# vme_sys_buff.net
KiCad netlist of a schematic drawn in Altium Designer
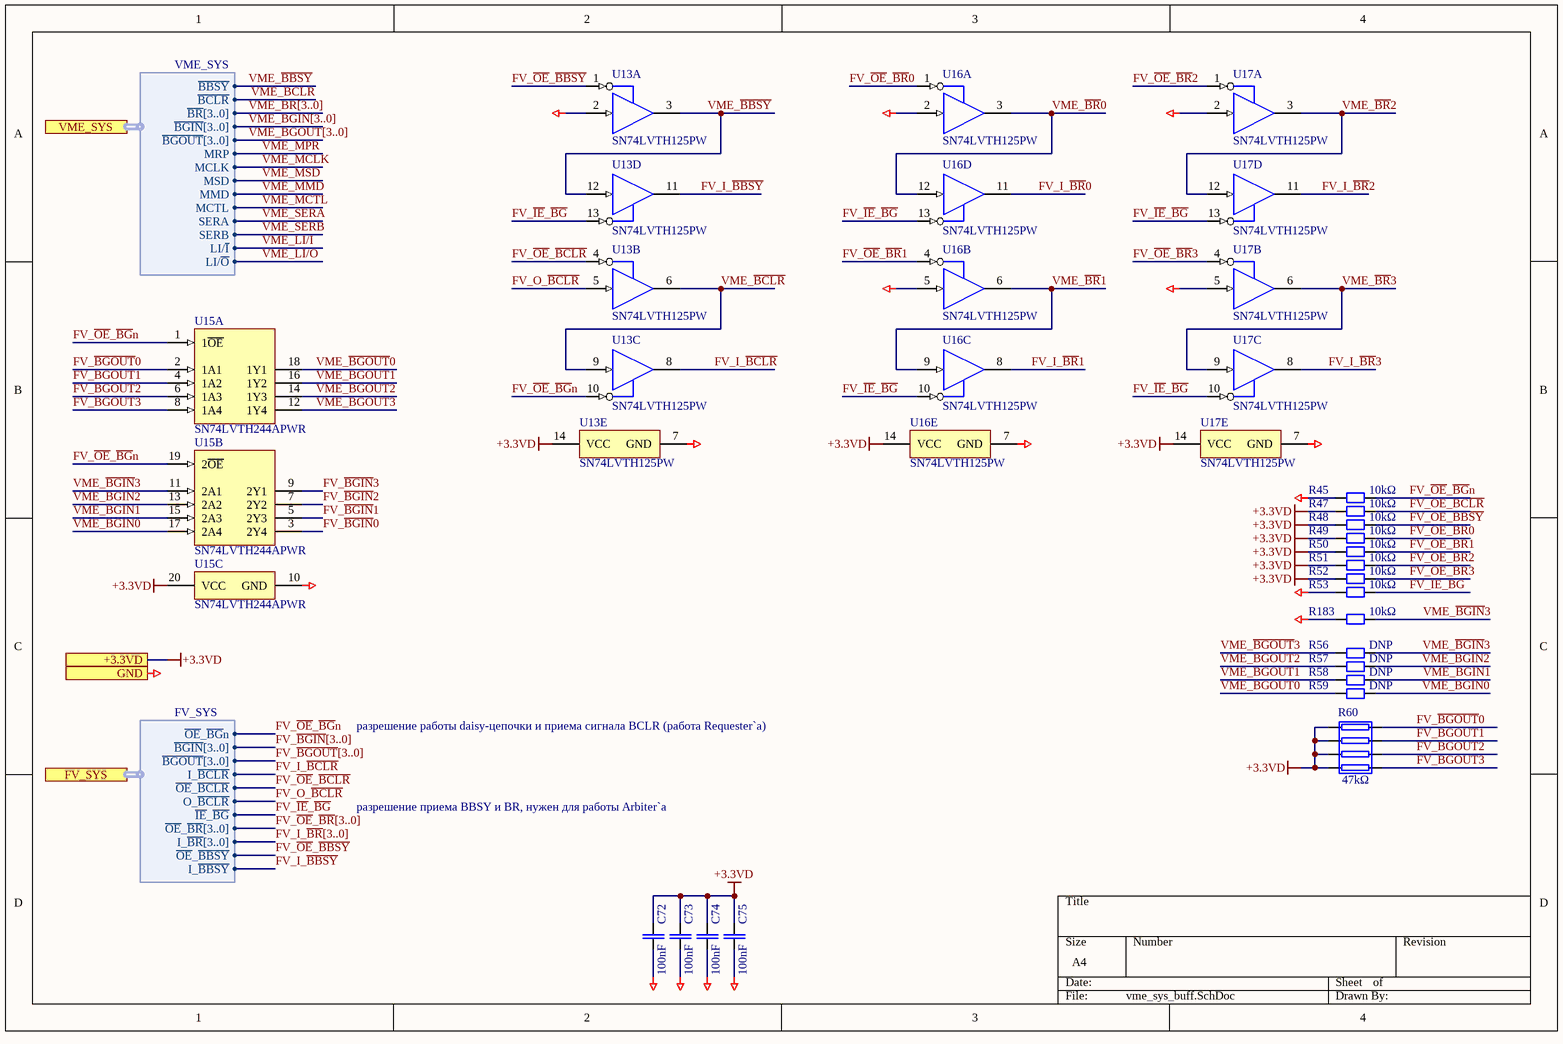
[diagram p0: vme_sys_buff.SchDoc]

(export (version "E")
  (design (tool "Eeschema 10.0.6"))
  (components
    (comp (ref "C72")
      (value "100nF")
      (footprint "CAPC1608N")
      (description "Generic ceramic SMD capacitor")
      (fields (field (name "MAINTAINER") "Evgeniy Kotov"))
      (libsource (lib "[Capacitors] Capacitors SMD") (part "CAPC"))
    )
    (comp (ref "C73")
      (value "100nF")
      (footprint "CAPC1608N")
      (description "Generic ceramic SMD capacitor")
      (fields (field (name "MAINTAINER") "Evgeniy Kotov"))
      (libsource (lib "[Capacitors] Capacitors SMD") (part "CAPC"))
    )
    (comp (ref "C74")
      (value "100nF")
      (footprint "CAPC1608N")
      (description "Generic ceramic SMD capacitor")
      (fields (field (name "MAINTAINER") "Evgeniy Kotov"))
      (libsource (lib "[Capacitors] Capacitors SMD") (part "CAPC"))
    )
    (comp (ref "C75")
      (value "100nF")
      (footprint "CAPC1608N")
      (description "Generic ceramic SMD capacitor")
      (fields (field (name "MAINTAINER") "Evgeniy Kotov"))
      (libsource (lib "[Capacitors] Capacitors SMD") (part "CAPC"))
    )
    (comp (ref "R45")
      (value "10kΩ")
      (footprint "RESC2012N")
      (description "Resistor, Generic, SMD")
      (fields (field (name "MAINTAINER") "Evgeniy Kotov"))
      (libsource (lib "[Resistors] Resistors SMD") (part "RESC"))
    )
    (comp (ref "R47")
      (value "10kΩ")
      (footprint "RESC2012N")
      (description "Resistor, Generic, SMD")
      (fields (field (name "MAINTAINER") "Evgeniy Kotov"))
      (libsource (lib "[Resistors] Resistors SMD") (part "RESC"))
    )
    (comp (ref "R48")
      (value "10kΩ")
      (footprint "RESC2012N")
      (description "Resistor, Generic, SMD")
      (fields (field (name "MAINTAINER") "Evgeniy Kotov"))
      (libsource (lib "[Resistors] Resistors SMD") (part "RESC"))
    )
    (comp (ref "R49")
      (value "10kΩ")
      (footprint "RESC2012N")
      (description "Resistor, Generic, SMD")
      (fields (field (name "MAINTAINER") "Evgeniy Kotov"))
      (libsource (lib "[Resistors] Resistors SMD") (part "RESC"))
    )
    (comp (ref "R50")
      (value "10kΩ")
      (footprint "RESC2012N")
      (description "Resistor, Generic, SMD")
      (fields (field (name "MAINTAINER") "Evgeniy Kotov"))
      (libsource (lib "[Resistors] Resistors SMD") (part "RESC"))
    )
    (comp (ref "R51")
      (value "10kΩ")
      (footprint "RESC2012N")
      (description "Resistor, Generic, SMD")
      (fields (field (name "MAINTAINER") "Evgeniy Kotov"))
      (libsource (lib "[Resistors] Resistors SMD") (part "RESC"))
    )
    (comp (ref "R52")
      (value "10kΩ")
      (footprint "RESC2012N")
      (description "Resistor, Generic, SMD")
      (fields (field (name "MAINTAINER") "Evgeniy Kotov"))
      (libsource (lib "[Resistors] Resistors SMD") (part "RESC"))
    )
    (comp (ref "R53")
      (value "10kΩ")
      (footprint "RESC2012N")
      (description "Resistor, Generic, SMD")
      (fields (field (name "MAINTAINER") "Evgeniy Kotov"))
      (libsource (lib "[Resistors] Resistors SMD") (part "RESC"))
    )
    (comp (ref "R56")
      (value "DNP")
      (footprint "RESC1608N")
      (description "Resistor, Generic, SMD")
      (fields (field (name "MAINTAINER") "Evgeniy Kotov"))
      (libsource (lib "[Resistors] Resistors SMD") (part "RESC"))
    )
    (comp (ref "R57")
      (value "DNP")
      (footprint "RESC1608N")
      (description "Resistor, Generic, SMD")
      (fields (field (name "MAINTAINER") "Evgeniy Kotov"))
      (libsource (lib "[Resistors] Resistors SMD") (part "RESC"))
    )
    (comp (ref "R58")
      (value "DNP")
      (footprint "RESC1608N")
      (description "Resistor, Generic, SMD")
      (fields (field (name "MAINTAINER") "Evgeniy Kotov"))
      (libsource (lib "[Resistors] Resistors SMD") (part "RESC"))
    )
    (comp (ref "R59")
      (value "DNP")
      (footprint "RESC1608N")
      (description "Resistor, Generic, SMD")
      (fields (field (name "MAINTAINER") "Evgeniy Kotov"))
      (libsource (lib "[Resistors] Resistors SMD") (part "RESC"))
    )
    (comp (ref "R60")
      (value "47kΩ")
      (footprint "CAY16-J4")
      (fields (field (name "Comment") "CAY16-4702F4LF") (field (name "MAINTAINER") "Anton Pavlenko"))
      (libsource (lib "[Resistors] Resistors SMD") (part "RESPACK4"))
    )
    (comp (ref "R183")
      (value "10kΩ")
      (footprint "RESC2012N")
      (description "Resistor, Generic, SMD")
      (fields (field (name "MAINTAINER") "Evgeniy Kotov"))
      (libsource (lib "[Resistors] Resistors SMD") (part "RESC"))
    )
    (comp (ref "U13")
      (value "SN74LVTH125PW")
      (footprint "PW0014A_N")
      (description "3.3-V ABT Quadruple Bus Buffers With 3-State Outputs, PW0014A, TUBE")
      (fields
        (field (name "MANUFACTURER") "Texas Instruments")
        (field (name "GENERIC PART NUMBER") "SN74LVTH125")
      )
      (libsource (lib "") (part "TI-SN74LVTH125-PW0014A-14_1"))
    )
    (comp (ref "U15")
      (value "SN74LVTH244APWR")
      (footprint "PW0020A_N")
      (description "3.3-V ABT Octal Buffers/Drivers With 3-State Outputs, PW0020A, LARGE T&R")
      (fields
        (field (name "GENERIC PART NUMBER") "SN74LVTH244A")
        (field (name "MANUFACTURER") "Texas Instruments")
      )
      (libsource (lib "Altium Content Vault") (part "TI-SN54_74-XX020A-20"))
    )
    (comp (ref "U16")
      (value "SN74LVTH125PW")
      (footprint "PW0014A_N")
      (description "3.3-V ABT Quadruple Bus Buffers With 3-State Outputs, PW0014A, TUBE")
      (fields
        (field (name "MANUFACTURER") "Texas Instruments")
        (field (name "GENERIC PART NUMBER") "SN74LVTH125")
      )
      (libsource (lib "Altium Content Vault") (part "TI-SN74LVTH125-PW0014A-14"))
    )
    (comp (ref "U17")
      (value "SN74LVTH125PW")
      (footprint "PW0014A_N")
      (description "3.3-V ABT Quadruple Bus Buffers With 3-State Outputs, PW0014A, TUBE")
      (fields
        (field (name "MANUFACTURER") "Texas Instruments")
        (field (name "GENERIC PART NUMBER") "SN74LVTH125")
      )
      (libsource (lib "") (part "TI-SN74LVTH125-PW0014A-14_1"))
    )
  )
  (nets
    (net (code "3") (name "+3.3VD") (class "Default")
      (node (ref "C72") (pin "2") (pintype "passive"))
      (node (ref "C73") (pin "2") (pintype "passive"))
      (node (ref "C74") (pin "2") (pintype "passive"))
      (node (ref "C75") (pin "2") (pintype "passive"))
      (node (ref "R47") (pin "1") (pintype "passive"))
      (node (ref "R48") (pin "1") (pintype "passive"))
      (node (ref "R49") (pin "1") (pintype "passive"))
      (node (ref "R50") (pin "1") (pintype "passive"))
      (node (ref "R51") (pin "1") (pintype "passive"))
      (node (ref "R52") (pin "1") (pintype "passive"))
      (node (ref "R60") (pin "1") (pinfunction "1_1") (pintype "passive"))
      (node (ref "R60") (pin "2") (pinfunction "2_2") (pintype "passive"))
      (node (ref "R60") (pin "3") (pinfunction "3_3") (pintype "passive"))
      (node (ref "R60") (pin "4") (pinfunction "4_4") (pintype "passive"))
      (node (ref "U13") (pin "14") (pinfunction "VCC_14") (pintype "power_in"))
      (node (ref "U15") (pin "20") (pinfunction "VCC_20") (pintype "power_in"))
      (node (ref "U16") (pin "14") (pinfunction "VCC_14") (pintype "power_in"))
      (node (ref "U17") (pin "14") (pinfunction "VCC_14") (pintype "power_in"))
    )
    (net (code "4") (name "/FV_I_~{BBSY}") (class "Default")
      (node (ref "U13") (pin "11") (pinfunction "4Y_11") (pintype "tri_state"))
    )
    (net (code "5") (name "/FV_I_~{BCLR}") (class "Default")
      (node (ref "U13") (pin "8") (pinfunction "3Y_8") (pintype "tri_state"))
    )
    (net (code "6") (name "/FV_I_~{BR}0") (class "Default")
      (node (ref "U16") (pin "11") (pinfunction "4Y_11") (pintype "tri_state"))
    )
    (net (code "7") (name "/FV_I_~{BR}1") (class "Default")
      (node (ref "U16") (pin "8") (pinfunction "3Y_8") (pintype "tri_state"))
    )
    (net (code "8") (name "/FV_I_~{BR}2") (class "Default")
      (node (ref "U17") (pin "11") (pinfunction "4Y_11") (pintype "tri_state"))
    )
    (net (code "9") (name "/FV_I_~{BR}3") (class "Default")
      (node (ref "U17") (pin "8") (pinfunction "3Y_8") (pintype "tri_state"))
    )
    (net (code "11") (name "/FV_O_~{BCLR}") (class "Default")
      (node (ref "U13") (pin "5") (pinfunction "2A_5") (pintype "input"))
    )
    (net (code "13") (name "/FV_~{BGIN}0") (class "Default")
      (node (ref "U15") (pin "3") (pinfunction "2Y4_3") (pintype "tri_state"))
    )
    (net (code "14") (name "/FV_~{BGIN}1") (class "Default")
      (node (ref "U15") (pin "5") (pinfunction "2Y3_5") (pintype "tri_state"))
    )
    (net (code "15") (name "/FV_~{BGIN}2") (class "Default")
      (node (ref "U15") (pin "7") (pinfunction "2Y2_7") (pintype "tri_state"))
    )
    (net (code "16") (name "/FV_~{BGIN}3") (class "Default")
      (node (ref "U15") (pin "9") (pinfunction "2Y1_9") (pintype "tri_state"))
    )
    (net (code "17") (name "/FV_~{BGOUT}0") (class "Default")
      (node (ref "R60") (pin "5") (pinfunction "5_5") (pintype "passive"))
      (node (ref "U15") (pin "2") (pinfunction "1A1_2") (pintype "input"))
    )
    (net (code "18") (name "/FV_~{BGOUT}1") (class "Default")
      (node (ref "R60") (pin "6") (pinfunction "6_6") (pintype "passive"))
      (node (ref "U15") (pin "4") (pinfunction "1A2_4") (pintype "input"))
    )
    (net (code "19") (name "/FV_~{BGOUT}2") (class "Default")
      (node (ref "R60") (pin "7") (pinfunction "7_7") (pintype "passive"))
      (node (ref "U15") (pin "6") (pinfunction "1A3_6") (pintype "input"))
    )
    (net (code "20") (name "/FV_~{BGOUT}3") (class "Default")
      (node (ref "R60") (pin "8") (pinfunction "8_8") (pintype "passive"))
      (node (ref "U15") (pin "8") (pinfunction "1A4_8") (pintype "input"))
    )
    (net (code "22") (name "/FV_~{IE}_~{BG}") (class "Default")
      (node (ref "R53") (pin "2") (pintype "passive"))
      (node (ref "U13") (pin "13") (pinfunction "4~{OE}_13") (pintype "input"))
      (node (ref "U16") (pin "10") (pinfunction "3~{OE}_10") (pintype "input"))
      (node (ref "U16") (pin "13") (pinfunction "4~{OE}_13") (pintype "input"))
      (node (ref "U17") (pin "10") (pinfunction "3~{OE}_10") (pintype "input"))
      (node (ref "U17") (pin "13") (pinfunction "4~{OE}_13") (pintype "input"))
    )
    (net (code "23") (name "/FV_~{OE}_~{BBSY}") (class "Default")
      (node (ref "R48") (pin "2") (pintype "passive"))
      (node (ref "U13") (pin "1") (pinfunction "1~{OE}_1") (pintype "input"))
    )
    (net (code "24") (name "/FV_~{OE}_~{BCLR}") (class "Default")
      (node (ref "R47") (pin "2") (pintype "passive"))
      (node (ref "U13") (pin "4") (pinfunction "2~{OE}_4") (pintype "input"))
    )
    (net (code "25") (name "/FV_~{OE}_~{BG}n") (class "Default")
      (node (ref "R45") (pin "2") (pintype "passive"))
      (node (ref "U13") (pin "10") (pinfunction "3~{OE}_10") (pintype "input"))
      (node (ref "U15") (pin "1") (pinfunction "1~{OE}_1") (pintype "input"))
      (node (ref "U15") (pin "19") (pinfunction "2~{OE}_19") (pintype "input"))
    )
    (net (code "26") (name "/FV_~{OE}_~{BR}0") (class "Default")
      (node (ref "R49") (pin "2") (pintype "passive"))
      (node (ref "U16") (pin "1") (pinfunction "1~{OE}_1") (pintype "input"))
    )
    (net (code "27") (name "/FV_~{OE}_~{BR}1") (class "Default")
      (node (ref "R50") (pin "2") (pintype "passive"))
      (node (ref "U16") (pin "4") (pinfunction "2~{OE}_4") (pintype "input"))
    )
    (net (code "28") (name "/FV_~{OE}_~{BR}2") (class "Default")
      (node (ref "R51") (pin "2") (pintype "passive"))
      (node (ref "U17") (pin "1") (pinfunction "1~{OE}_1") (pintype "input"))
    )
    (net (code "29") (name "/FV_~{OE}_~{BR}3") (class "Default")
      (node (ref "R52") (pin "2") (pintype "passive"))
      (node (ref "U17") (pin "4") (pinfunction "2~{OE}_4") (pintype "input"))
    )
    (net (code "41") (name "/VME_~{BBSY}") (class "Default")
      (node (ref "U13") (pin "12") (pinfunction "4A_12") (pintype "input"))
      (node (ref "U13") (pin "3") (pinfunction "1Y_3") (pintype "tri_state"))
    )
    (net (code "42") (name "/VME_~{BCLR}") (class "Default")
      (node (ref "U13") (pin "6") (pinfunction "2Y_6") (pintype "tri_state"))
      (node (ref "U13") (pin "9") (pinfunction "3A_9") (pintype "input"))
    )
    (net (code "43") (name "/VME_~{BGIN}0") (class "Default")
      (node (ref "R59") (pin "2") (pintype "passive"))
      (node (ref "U15") (pin "17") (pinfunction "2A4_17") (pintype "input"))
    )
    (net (code "44") (name "/VME_~{BGIN}1") (class "Default")
      (node (ref "R58") (pin "2") (pintype "passive"))
      (node (ref "U15") (pin "15") (pinfunction "2A3_15") (pintype "input"))
    )
    (net (code "45") (name "/VME_~{BGIN}2") (class "Default")
      (node (ref "R57") (pin "2") (pintype "passive"))
      (node (ref "U15") (pin "13") (pinfunction "2A2_13") (pintype "input"))
    )
    (net (code "46") (name "/VME_~{BGIN}3") (class "Default")
      (node (ref "R183") (pin "2") (pintype "passive"))
      (node (ref "R56") (pin "2") (pintype "passive"))
      (node (ref "U15") (pin "11") (pinfunction "2A1_11") (pintype "input"))
    )
    (net (code "48") (name "/VME_~{BGOUT}0") (class "Default")
      (node (ref "R59") (pin "1") (pintype "passive"))
      (node (ref "U15") (pin "18") (pinfunction "1Y1_18") (pintype "tri_state"))
    )
    (net (code "49") (name "/VME_~{BGOUT}1") (class "Default")
      (node (ref "R58") (pin "1") (pintype "passive"))
      (node (ref "U15") (pin "16") (pinfunction "1Y2_16") (pintype "tri_state"))
    )
    (net (code "50") (name "/VME_~{BGOUT}2") (class "Default")
      (node (ref "R57") (pin "1") (pintype "passive"))
      (node (ref "U15") (pin "14") (pinfunction "1Y3_14") (pintype "tri_state"))
    )
    (net (code "51") (name "/VME_~{BGOUT}3") (class "Default")
      (node (ref "R56") (pin "1") (pintype "passive"))
      (node (ref "U15") (pin "12") (pinfunction "1Y4_12") (pintype "tri_state"))
    )
    (net (code "52") (name "/VME_~{BR}0") (class "Default")
      (node (ref "U16") (pin "12") (pinfunction "4A_12") (pintype "input"))
      (node (ref "U16") (pin "3") (pinfunction "1Y_3") (pintype "tri_state"))
    )
    (net (code "53") (name "/VME_~{BR}1") (class "Default")
      (node (ref "U16") (pin "6") (pinfunction "2Y_6") (pintype "tri_state"))
      (node (ref "U16") (pin "9") (pinfunction "3A_9") (pintype "input"))
    )
    (net (code "54") (name "/VME_~{BR}2") (class "Default")
      (node (ref "U17") (pin "12") (pinfunction "4A_12") (pintype "input"))
      (node (ref "U17") (pin "3") (pinfunction "1Y_3") (pintype "tri_state"))
    )
    (net (code "55") (name "/VME_~{BR}3") (class "Default")
      (node (ref "U17") (pin "6") (pinfunction "2Y_6") (pintype "tri_state"))
      (node (ref "U17") (pin "9") (pinfunction "3A_9") (pintype "input"))
    )
    (net (code "59") (name "GND") (class "Default")
      (node (ref "C72") (pin "1") (pintype "passive"))
      (node (ref "C73") (pin "1") (pintype "passive"))
      (node (ref "C74") (pin "1") (pintype "passive"))
      (node (ref "C75") (pin "1") (pintype "passive"))
      (node (ref "R183") (pin "1") (pintype "passive"))
      (node (ref "R45") (pin "1") (pintype "passive"))
      (node (ref "R53") (pin "1") (pintype "passive"))
      (node (ref "U13") (pin "2") (pinfunction "1A_2") (pintype "input"))
      (node (ref "U13") (pin "7") (pinfunction "GND_7") (pintype "power_in"))
      (node (ref "U15") (pin "10") (pinfunction "GND_10") (pintype "power_in"))
      (node (ref "U16") (pin "2") (pinfunction "1A_2") (pintype "input"))
      (node (ref "U16") (pin "5") (pinfunction "2A_5") (pintype "input"))
      (node (ref "U16") (pin "7") (pinfunction "GND_7") (pintype "power_in"))
      (node (ref "U17") (pin "2") (pinfunction "1A_2") (pintype "input"))
      (node (ref "U17") (pin "5") (pinfunction "2A_5") (pintype "input"))
      (node (ref "U17") (pin "7") (pinfunction "GND_7") (pintype "power_in"))
    )
  )
)
